# Sheet2.net
KiCad netlist of a schematic drawn in Altium Designer
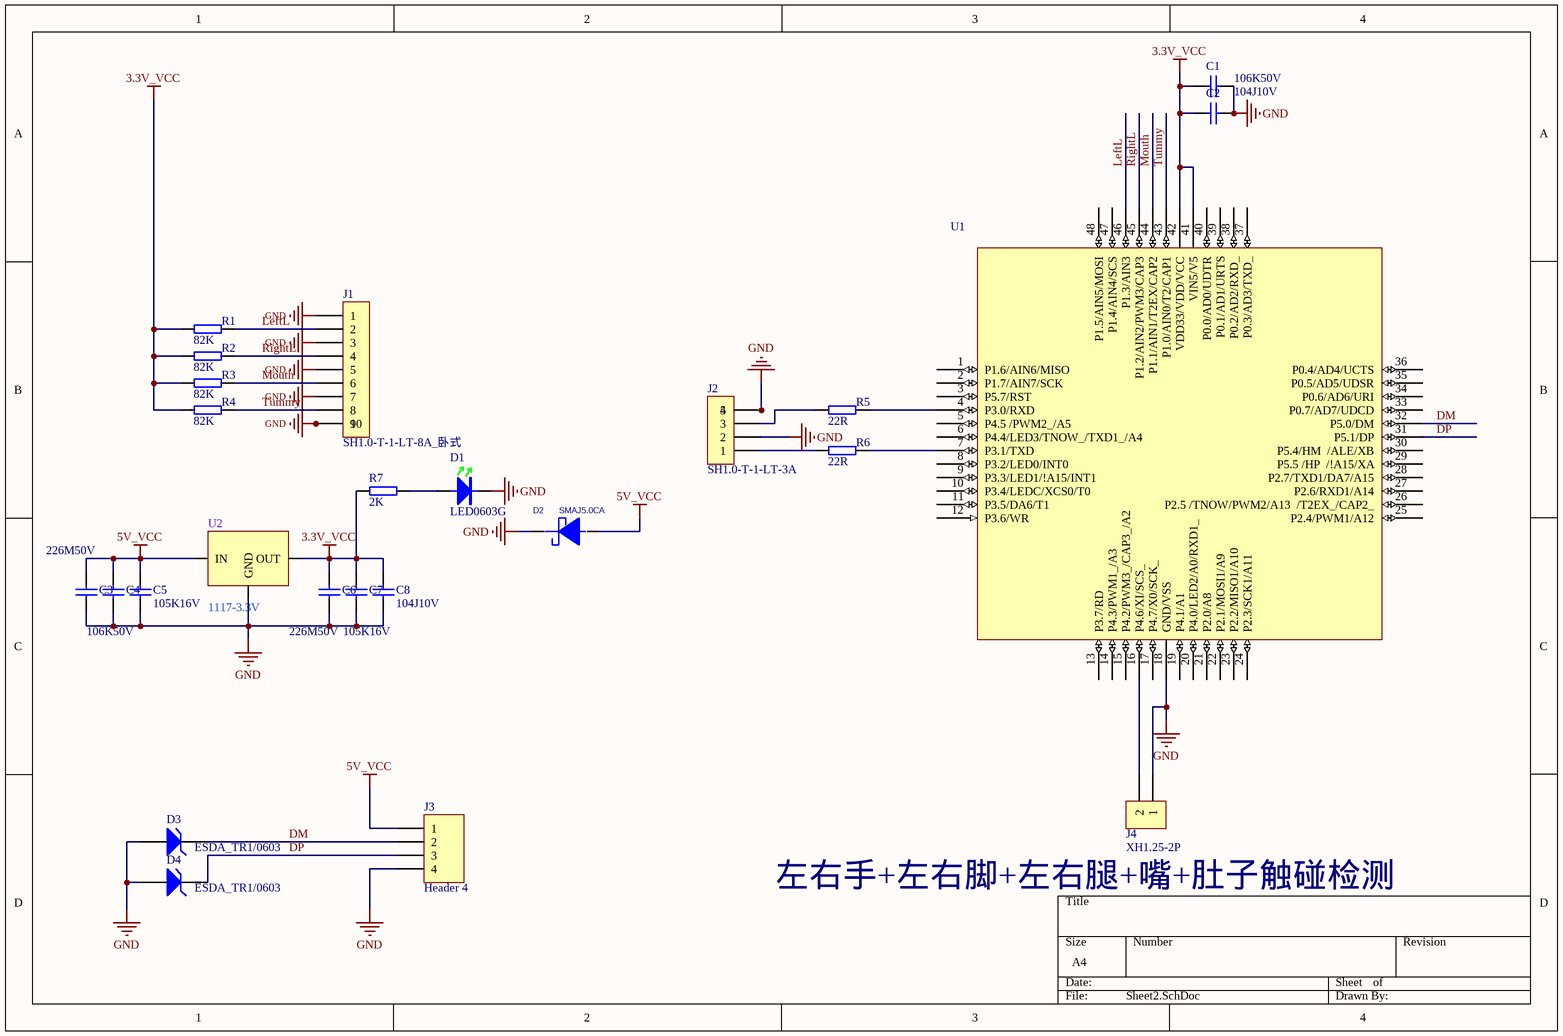
[diagram p0: Sheet2.SchDoc]

(export (version "E")
  (design (tool "Eeschema 10.0.6"))
  (components
    (comp (ref "C1")
      (value "106K50V")
      (footprint "C0603")
      (description "贴片电容-陶瓷")
      (libsource (lib "AIWAC-bolsterV01") (part "C0603X7R-106K50V"))
    )
    (comp (ref "C2")
      (value "104J10V")
      (footprint "C0402")
      (description "贴片电容-陶瓷")
      (libsource (lib "AIWAC-bolsterV01") (part "C0402X7R-104J10V"))
    )
    (comp (ref "C3")
      (value "226M50V")
      (footprint "C0805")
      (description "贴片电容-陶瓷")
      (libsource (lib "AIWAC-bolsterV01") (part "C0805Y5V-226M50V"))
    )
    (comp (ref "C4")
      (value "106K50V")
      (footprint "C0603")
      (description "贴片电容-陶瓷")
      (libsource (lib "AIWAC-bolsterV01") (part "C0603X7R-106K50V"))
    )
    (comp (ref "C5")
      (value "105K16V")
      (footprint "C0603")
      (description "贴片电容-陶瓷")
      (libsource (lib "AIWAC-bolsterV01") (part "C0603X7R-105K16V"))
    )
    (comp (ref "C6")
      (value "226M50V")
      (footprint "C0805")
      (description "贴片电容-陶瓷")
      (libsource (lib "AIWAC-bolsterV01") (part "C0805Y5V-226M50V"))
    )
    (comp (ref "C7")
      (value "105K16V")
      (footprint "C0603")
      (description "贴片电容-陶瓷")
      (libsource (lib "AIWAC-bolsterV01") (part "C0603X7R-105K16V"))
    )
    (comp (ref "C8")
      (value "104J10V")
      (footprint "C0402")
      (description "贴片电容-陶瓷")
      (libsource (lib "AIWAC-bolsterV01") (part "C0402X7R-104J10V"))
    )
    (comp (ref "D1")
      (value "LED0603G")
      (footprint "D-LED0603G")
      (description "贴片二极管-LED")
      (libsource (lib "AIWAC-bolsterV01") (part "DLED-0603-G"))
    )
    (comp (ref "D2")
      (value "SMAJ5.0CA")
      (footprint "PCB11:DO-214")
      (libsource (lib "ISO-V3") (part "SMAJ5.0CA"))
    )
    (comp (ref "D3")
      (value "ESDA_TR1/0603")
      (footprint "HS_0603D")
      (description "Zener Diode")
      (fields (field (name "PUBLISHER") "*"))
      (libsource (lib "HSC32K1(QFN56)_BlueTooth_V2.0_20171108 - 副本") (part "D Zener"))
    )
    (comp (ref "D4")
      (value "ESDA_TR1/0603")
      (footprint "HS_0603D")
      (description "Zener Diode")
      (fields (field (name "PUBLISHER") "*"))
      (libsource (lib "HSC32K1(QFN56)_BlueTooth_V2.0_20171108 - 副本") (part "D Zener"))
    )
    (comp (ref "J1")
      (value "SH1.0-T-1-LT-8A_卧式")
      (footprint "J-SH1.0-T-1-LT-8A_卧式")
      (description "SH1.0-T-1-LT-6A_卧式")
      (libsource (lib "Connector") (part "SH1.0-T-1-LT-8A_卧式"))
    )
    (comp (ref "J2")
      (value "SH1.0-T-1-LT-3A")
      (footprint "AIWAC-TF_CARD-V02:J-SH1.0-T-1-LT-3A")
      (description "接插件-SH1.0-T-1-LT-3A")
      (libsource (lib "Connector") (part "SH1.0-T-1-LT-3A"))
    )
    (comp (ref "J3")
      (value "Header 4")
      (footprint "USB-AB")
      (description "Header, 4-Pin")
      (fields (field (name "PUBLISHER") "Altium Limited"))
      (libsource (lib "Miscellaneous Connectors") (part "Header 4"))
    )
    (comp (ref "J4")
      (value "XH1.25-2P")
      (footprint "PCB1:S1.25-2P")
      (description "接插件-2.54")
      (libsource (lib "AIWAC-bolsterV01") (part "J-XH2.54-2P"))
    )
    (comp (ref "R1")
      (value "82K")
      (footprint "R0603")
      (description "贴片电阻-通用")
      (libsource (lib "Resistor") (part "R0603-100RF"))
    )
    (comp (ref "R2")
      (value "82K")
      (footprint "R0603")
      (description "贴片电阻-通用")
      (libsource (lib "Resistor") (part "R0603-100RF"))
    )
    (comp (ref "R3")
      (value "82K")
      (footprint "R0603")
      (description "贴片电阻-通用")
      (libsource (lib "Resistor") (part "R0603-100RF"))
    )
    (comp (ref "R4")
      (value "82K")
      (footprint "R0603")
      (description "贴片电阻-通用")
      (libsource (lib "Resistor") (part "R0603-100RF"))
    )
    (comp (ref "R5")
      (value "22R")
      (footprint "R0603")
      (description "贴片电阻-通用")
      (libsource (lib "Resistor") (part "R0603-100RF"))
    )
    (comp (ref "R6")
      (value "22R")
      (footprint "R0603")
      (description "贴片电阻-通用")
      (libsource (lib "Resistor") (part "R0603-100RF"))
    )
    (comp (ref "R7")
      (value "2K")
      (footprint "R0603")
      (description "贴片电阻-通用")
      (libsource (lib "Resistor") (part "R0603-100RF"))
    )
    (comp (ref "U1")
      (value "CH559L")
      (footprint "LQFP48")
      (description "单片机")
      (libsource (lib "AIWAC-bolsterV01") (part "CH559L"))
    )
    (comp (ref "U2")
      (value "1117-3.3V")
      (footprint "SOT-223")
      (description "芯片 电源类")
      (libsource (lib "标准通用原理图库") (part "AP1117-33 SOT-223"))
    )
  )
  (nets
    (net (code "1") (name "/DM") (class "Default")
      (node (ref "D3") (pin "2") (pinfunction "K_2") (pintype "passive"))
      (node (ref "J3") (pin "2") (pinfunction "2_2") (pintype "passive"))
      (node (ref "U1") (pin "32") (pinfunction "P5.0/DM_32") (pintype "bidirectional"))
    )
    (net (code "2") (name "/DP") (class "Default")
      (node (ref "D4") (pin "2") (pinfunction "K_2") (pintype "passive"))
      (node (ref "J3") (pin "3") (pinfunction "3_3") (pintype "passive"))
      (node (ref "U1") (pin "31") (pinfunction "P5.1/DP_31") (pintype "bidirectional"))
    )
    (net (code "3") (name "/LeftL") (class "Default")
      (node (ref "J1") (pin "2") (pinfunction "2_2") (pintype "passive"))
      (node (ref "R1") (pin "2") (pinfunction "2_2") (pintype "passive"))
      (node (ref "U1") (pin "46") (pinfunction "P1.3/AIN3_46") (pintype "bidirectional"))
    )
    (net (code "4") (name "/Mouth") (class "Default")
      (node (ref "J1") (pin "6") (pinfunction "6_6") (pintype "passive"))
      (node (ref "R3") (pin "2") (pinfunction "2_2") (pintype "passive"))
      (node (ref "U1") (pin "44") (pinfunction "P1.1/AIN1/T2EX/CAP2_44") (pintype "bidirectional"))
    )
    (net (code "5") (name "/RightL") (class "Default")
      (node (ref "J1") (pin "4") (pinfunction "4_4") (pintype "passive"))
      (node (ref "R2") (pin "2") (pinfunction "2_2") (pintype "passive"))
      (node (ref "U1") (pin "45") (pinfunction "P1.2/AIN2/PWM3/CAP3_45") (pintype "bidirectional"))
    )
    (net (code "6") (name "/Tummy") (class "Default")
      (node (ref "J1") (pin "8") (pinfunction "8_8") (pintype "passive"))
      (node (ref "R4") (pin "2") (pinfunction "2_2") (pintype "passive"))
      (node (ref "U1") (pin "43") (pinfunction "P1.0/AIN0/T2/CAP1_43") (pintype "bidirectional"))
    )
    (net (code "7") (name "3.3V_VCC") (class "Default")
      (node (ref "C1") (pin "2") (pinfunction "2_2") (pintype "passive"))
      (node (ref "C2") (pin "2") (pinfunction "2_2") (pintype "passive"))
      (node (ref "C6") (pin "1") (pinfunction "1_1") (pintype "passive"))
      (node (ref "C7") (pin "2") (pinfunction "2_2") (pintype "passive"))
      (node (ref "C8") (pin "1") (pinfunction "1_1") (pintype "passive"))
      (node (ref "R1") (pin "1") (pinfunction "1_1") (pintype "passive"))
      (node (ref "R2") (pin "1") (pinfunction "1_1") (pintype "passive"))
      (node (ref "R3") (pin "1") (pinfunction "1_1") (pintype "passive"))
      (node (ref "R4") (pin "1") (pinfunction "1_1") (pintype "passive"))
      (node (ref "R7") (pin "2") (pinfunction "2_2") (pintype "passive"))
      (node (ref "U1") (pin "41") (pinfunction "VIN5/V5_41") (pintype "passive"))
      (node (ref "U1") (pin "42") (pinfunction "VDD33/VDD/VCC_42") (pintype "passive"))
      (node (ref "U2") (pin "2") (pinfunction "OUT_2") (pintype "passive"))
    )
    (net (code "8") (name "5V_VCC") (class "Default")
      (node (ref "C3") (pin "1") (pinfunction "1_1") (pintype "passive"))
      (node (ref "C4") (pin "1") (pinfunction "1_1") (pintype "passive"))
      (node (ref "C5") (pin "1") (pinfunction "1_1") (pintype "passive"))
      (node (ref "D2") (pin "1") (pinfunction "+_1") (pintype "passive"))
      (node (ref "J3") (pin "1") (pinfunction "1_1") (pintype "passive"))
      (node (ref "U2") (pin "3") (pinfunction "IN_3") (pintype "passive"))
    )
    (net (code "9") (name "GND") (class "Default")
      (node (ref "C1") (pin "1") (pinfunction "1_1") (pintype "passive"))
      (node (ref "C2") (pin "1") (pinfunction "1_1") (pintype "passive"))
      (node (ref "C3") (pin "2") (pinfunction "2_2") (pintype "passive"))
      (node (ref "C4") (pin "2") (pinfunction "2_2") (pintype "passive"))
      (node (ref "C5") (pin "2") (pinfunction "2_2") (pintype "passive"))
      (node (ref "C6") (pin "2") (pinfunction "2_2") (pintype "passive"))
      (node (ref "C7") (pin "1") (pinfunction "1_1") (pintype "passive"))
      (node (ref "C8") (pin "2") (pinfunction "2_2") (pintype "passive"))
      (node (ref "D1") (pin "2") (pinfunction "2_2") (pintype "passive"))
      (node (ref "D2") (pin "2") (pinfunction "-_2") (pintype "passive"))
      (node (ref "D3") (pin "1") (pinfunction "A_1") (pintype "passive"))
      (node (ref "D4") (pin "1") (pinfunction "A_1") (pintype "passive"))
      (node (ref "J1") (pin "1") (pinfunction "1_1") (pintype "passive"))
      (node (ref "J1") (pin "10") (pinfunction "10_10") (pintype "passive"))
      (node (ref "J1") (pin "3") (pinfunction "3_3") (pintype "passive"))
      (node (ref "J1") (pin "5") (pinfunction "5_5") (pintype "passive"))
      (node (ref "J1") (pin "7") (pinfunction "7_7") (pintype "passive"))
      (node (ref "J1") (pin "9") (pinfunction "9_9") (pintype "passive"))
      (node (ref "J2") (pin "2") (pinfunction "2_2") (pintype "passive"))
      (node (ref "J2") (pin "4") (pinfunction "4_4") (pintype "passive"))
      (node (ref "J2") (pin "5") (pinfunction "5_5") (pintype "passive"))
      (node (ref "J3") (pin "4") (pinfunction "4_4") (pintype "passive"))
      (node (ref "J4") (pin "1") (pinfunction "1_1") (pintype "passive"))
      (node (ref "U1") (pin "18") (pinfunction "GND/VSS_18") (pintype "passive"))
      (node (ref "U2") (pin "1") (pinfunction "GND_1") (pintype "passive"))
    )
    (net (code "10") (name "Net-(D1-Pad1)") (class "Default")
      (node (ref "D1") (pin "1") (pinfunction "1_1") (pintype "passive"))
      (node (ref "R7") (pin "1") (pinfunction "1_1") (pintype "passive"))
    )
    (net (code "11") (name "Net-(J2-Pad1)") (class "Default")
      (node (ref "J2") (pin "1") (pinfunction "1_1") (pintype "passive"))
      (node (ref "R6") (pin "1") (pinfunction "1_1") (pintype "passive"))
    )
    (net (code "12") (name "Net-(J2-Pad3)") (class "Default")
      (node (ref "J2") (pin "3") (pinfunction "3_3") (pintype "passive"))
      (node (ref "R5") (pin "1") (pinfunction "1_1") (pintype "passive"))
    )
    (net (code "13") (name "Net-(U1-P3.0{slash}RXD)") (class "Default")
      (node (ref "R5") (pin "2") (pinfunction "2_2") (pintype "passive"))
      (node (ref "U1") (pin "4") (pinfunction "P3.0/RXD_4") (pintype "bidirectional"))
    )
    (net (code "14") (name "Net-(U1-P3.1{slash}TXD)") (class "Default")
      (node (ref "R6") (pin "2") (pinfunction "2_2") (pintype "passive"))
      (node (ref "U1") (pin "7") (pinfunction "P3.1/TXD_7") (pintype "bidirectional"))
    )
    (net (code "15") (name "Net-(U1-P4.6{slash}XI{slash}SCS_)") (class "Default")
      (node (ref "J4") (pin "2") (pinfunction "2_2") (pintype "passive"))
      (node (ref "U1") (pin "16") (pinfunction "P4.6/XI/SCS__16") (pintype "bidirectional"))
    )
    (net (code "16") (name "unconnected-(U1-P0.0{slash}AD0{slash}UDTR-Pad40)") (class "Default")
      (node (ref "U1") (pin "40") (pinfunction "P0.0/AD0/UDTR_40") (pintype "bidirectional"))
    )
    (net (code "17") (name "unconnected-(U1-P0.1{slash}AD1{slash}URTS-Pad39)") (class "Default")
      (node (ref "U1") (pin "39") (pinfunction "P0.1/AD1/URTS_39") (pintype "bidirectional"))
    )
    (net (code "18") (name "unconnected-(U1-P0.2{slash}AD2{slash}RXD_-Pad38)") (class "Default")
      (node (ref "U1") (pin "38") (pinfunction "P0.2/AD2/RXD__38") (pintype "bidirectional"))
    )
    (net (code "19") (name "unconnected-(U1-P0.3{slash}AD3{slash}TXD_-Pad37)") (class "Default")
      (node (ref "U1") (pin "37") (pinfunction "P0.3/AD3/TXD__37") (pintype "bidirectional"))
    )
    (net (code "20") (name "unconnected-(U1-P0.4{slash}AD4{slash}UCTS-Pad36)") (class "Default")
      (node (ref "U1") (pin "36") (pinfunction "P0.4/AD4/UCTS_36") (pintype "bidirectional"))
    )
    (net (code "21") (name "unconnected-(U1-P0.5{slash}AD5{slash}UDSR-Pad35)") (class "Default")
      (node (ref "U1") (pin "35") (pinfunction "P0.5/AD5/UDSR_35") (pintype "bidirectional"))
    )
    (net (code "22") (name "unconnected-(U1-P0.6{slash}AD6{slash}URI-Pad34)") (class "Default")
      (node (ref "U1") (pin "34") (pinfunction "P0.6/AD6/URI_34") (pintype "bidirectional"))
    )
    (net (code "23") (name "unconnected-(U1-P0.7{slash}AD7{slash}UDCD-Pad33)") (class "Default")
      (node (ref "U1") (pin "33") (pinfunction "P0.7/AD7/UDCD_33") (pintype "bidirectional"))
    )
    (net (code "24") (name "unconnected-(U1-P1.4{slash}AIN4{slash}SCS-Pad47)") (class "Default")
      (node (ref "U1") (pin "47") (pinfunction "P1.4/AIN4/SCS_47") (pintype "bidirectional"))
    )
    (net (code "25") (name "unconnected-(U1-P1.5{slash}AIN5{slash}MOSI-Pad48)") (class "Default")
      (node (ref "U1") (pin "48") (pinfunction "P1.5/AIN5/MOSI_48") (pintype "bidirectional"))
    )
    (net (code "26") (name "unconnected-(U1-P1.6{slash}AIN6{slash}MISO-Pad1)") (class "Default")
      (node (ref "U1") (pin "1") (pinfunction "P1.6/AIN6/MISO_1") (pintype "bidirectional"))
    )
    (net (code "27") (name "unconnected-(U1-P1.7{slash}AIN7{slash}SCK-Pad2)") (class "Default")
      (node (ref "U1") (pin "2") (pinfunction "P1.7/AIN7/SCK_2") (pintype "bidirectional"))
    )
    (net (code "28") (name "unconnected-(U1-P2.0{slash}A8-Pad21)") (class "Default")
      (node (ref "U1") (pin "21") (pinfunction "P2.0/A8_21") (pintype "bidirectional"))
    )
    (net (code "29") (name "unconnected-(U1-P2.1{slash}MOSI1{slash}A9-Pad22)") (class "Default")
      (node (ref "U1") (pin "22") (pinfunction "P2.1/MOSI1/A9_22") (pintype "bidirectional"))
    )
    (net (code "30") (name "unconnected-(U1-P2.2{slash}MISO1{slash}A10-Pad23)") (class "Default")
      (node (ref "U1") (pin "23") (pinfunction "P2.2/MISO1/A10_23") (pintype "bidirectional"))
    )
    (net (code "31") (name "unconnected-(U1-P2.3{slash}SCK1{slash}A11-Pad24)") (class "Default")
      (node (ref "U1") (pin "24") (pinfunction "P2.3/SCK1/A11_24") (pintype "bidirectional"))
    )
    (net (code "32") (name "unconnected-(U1-P2.4{slash}PWM1{slash}A12-Pad25)") (class "Default")
      (node (ref "U1") (pin "25") (pinfunction "P2.4/PWM1/A12_25") (pintype "bidirectional"))
    )
    (net (code "33") (name "unconnected-(U1-P2.5_{slash}TNOW{slash}PWM2{slash}A13__{slash}T2EX_{slash}CAP2_-Pad26)") (class "Default")
      (node (ref "U1") (pin "26") (pinfunction "P2.5_/TNOW/PWM2/A13__/T2EX_/CAP2__26") (pintype "bidirectional"))
    )
    (net (code "34") (name "unconnected-(U1-P2.6{slash}RXD1{slash}A14-Pad27)") (class "Default")
      (node (ref "U1") (pin "27") (pinfunction "P2.6/RXD1/A14_27") (pintype "bidirectional"))
    )
    (net (code "35") (name "unconnected-(U1-P2.7{slash}TXD1{slash}DA7{slash}A15-Pad28)") (class "Default")
      (node (ref "U1") (pin "28") (pinfunction "P2.7/TXD1/DA7/A15_28") (pintype "bidirectional"))
    )
    (net (code "36") (name "unconnected-(U1-P3.2{slash}LED0{slash}INT0-Pad8)") (class "Default")
      (node (ref "U1") (pin "8") (pinfunction "P3.2/LED0/INT0_8") (pintype "bidirectional"))
    )
    (net (code "37") (name "unconnected-(U1-P3.3{slash}LED1{slash}!A15{slash}INT1-Pad9)") (class "Default")
      (node (ref "U1") (pin "9") (pinfunction "P3.3/LED1/!A15/INT1_9") (pintype "bidirectional"))
    )
    (net (code "38") (name "unconnected-(U1-P3.4{slash}LEDC{slash}XCS0{slash}T0-Pad10)") (class "Default")
      (node (ref "U1") (pin "10") (pinfunction "P3.4/LEDC/XCS0/T0_10") (pintype "bidirectional"))
    )
    (net (code "39") (name "unconnected-(U1-P3.5{slash}DA6{slash}T1-Pad11)") (class "Default")
      (node (ref "U1") (pin "11") (pinfunction "P3.5/DA6/T1_11") (pintype "bidirectional"))
    )
    (net (code "40") (name "unconnected-(U1-P3.6{slash}WR-Pad12)") (class "Default")
      (node (ref "U1") (pin "12") (pinfunction "P3.6/WR_12") (pintype "input"))
    )
    (net (code "41") (name "unconnected-(U1-P3.7{slash}RD-Pad13)") (class "Default")
      (node (ref "U1") (pin "13") (pinfunction "P3.7/RD_13") (pintype "bidirectional"))
    )
    (net (code "42") (name "unconnected-(U1-P4.0{slash}LED2{slash}A0{slash}RXD1_-Pad20)") (class "Default")
      (node (ref "U1") (pin "20") (pinfunction "P4.0/LED2/A0/RXD1__20") (pintype "bidirectional"))
    )
    (net (code "43") (name "unconnected-(U1-P4.1{slash}A1-Pad19)") (class "Default")
      (node (ref "U1") (pin "19") (pinfunction "P4.1/A1_19") (pintype "bidirectional"))
    )
    (net (code "44") (name "unconnected-(U1-P4.2{slash}PWM3_{slash}CAP3_{slash}A2-Pad15)") (class "Default")
      (node (ref "U1") (pin "15") (pinfunction "P4.2/PWM3_/CAP3_/A2_15") (pintype "bidirectional"))
    )
    (net (code "45") (name "unconnected-(U1-P4.3{slash}PWM1_{slash}A3-Pad14)") (class "Default")
      (node (ref "U1") (pin "14") (pinfunction "P4.3/PWM1_/A3_14") (pintype "bidirectional"))
    )
    (net (code "46") (name "unconnected-(U1-P4.4{slash}LED3{slash}TNOW_{slash}TXD1_{slash}A4-Pad6)") (class "Default")
      (node (ref "U1") (pin "6") (pinfunction "P4.4/LED3/TNOW_/TXD1_/A4_6") (pintype "bidirectional"))
    )
    (net (code "47") (name "unconnected-(U1-P4.5_{slash}PWM2_{slash}A5-Pad5)") (class "Default")
      (node (ref "U1") (pin "5") (pinfunction "P4.5_/PWM2_/A5_5") (pintype "bidirectional"))
    )
    (net (code "48") (name "unconnected-(U1-P4.7{slash}X0{slash}SCK_-Pad17)") (class "Default")
      (node (ref "U1") (pin "17") (pinfunction "P4.7/X0/SCK__17") (pintype "bidirectional"))
    )
    (net (code "49") (name "unconnected-(U1-P5.4{slash}HM__{slash}ALE{slash}XB-Pad30)") (class "Default")
      (node (ref "U1") (pin "30") (pinfunction "P5.4/HM__/ALE/XB_30") (pintype "bidirectional"))
    )
    (net (code "50") (name "unconnected-(U1-P5.5_{slash}HP__{slash}!A15{slash}XA-Pad29)") (class "Default")
      (node (ref "U1") (pin "29") (pinfunction "P5.5_/HP__/!A15/XA_29") (pintype "bidirectional"))
    )
    (net (code "51") (name "unconnected-(U1-P5.7{slash}RST-Pad3)") (class "Default")
      (node (ref "U1") (pin "3") (pinfunction "P5.7/RST_3") (pintype "bidirectional"))
    )
  )
)
